# Power.net
KiCad netlist of a schematic drawn in Altium Designer
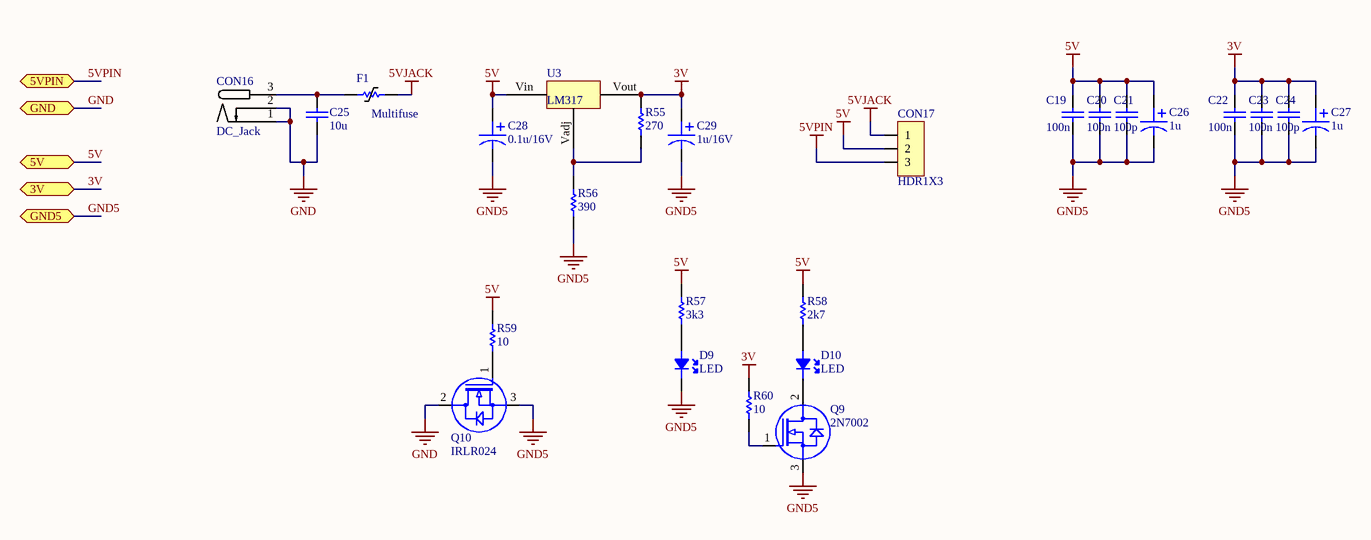
[diagram p0: Power.SchDoc]

(export (version "E")
  (design (tool "Eeschema 10.0.6"))
  (components
    (comp (ref "C19")
      (value "100n")
      (footprint "dimploma:0805C")
      (libsource (lib "diploma") (part "CAPACITOR"))
    )
    (comp (ref "C20")
      (value "100n")
      (footprint "dimploma:0805C")
      (libsource (lib "diploma") (part "CAPACITOR"))
    )
    (comp (ref "C21")
      (value "100p")
      (footprint "dimploma:0805C")
      (libsource (lib "diploma") (part "CAPACITOR"))
    )
    (comp (ref "C22")
      (value "100n")
      (footprint "dimploma:0805C")
      (libsource (lib "diploma") (part "CAPACITOR"))
    )
    (comp (ref "C23")
      (value "100n")
      (footprint "dimploma:0805C")
      (libsource (lib "diploma") (part "CAPACITOR"))
    )
    (comp (ref "C24")
      (value "100p")
      (footprint "dimploma:0805C")
      (libsource (lib "diploma") (part "CAPACITOR"))
    )
    (comp (ref "C25")
      (value "10u")
      (footprint "dimploma:0805C")
      (libsource (lib "diploma") (part "CAPACITOR"))
    )
    (comp (ref "C26")
      (value "1u")
      (footprint "dimploma:CA")
      (libsource (lib "diploma") (part "ELECTROLYTIC_CAPACITOR"))
    )
    (comp (ref "C27")
      (value "1u")
      (footprint "dimploma:CA")
      (libsource (lib "diploma") (part "ELECTROLYTIC_CAPACITOR"))
    )
    (comp (ref "C28")
      (value "0.1u/16V")
      (footprint "dimploma:CA")
      (libsource (lib "diploma") (part "ELECTROLYTIC_CAPACITOR"))
    )
    (comp (ref "C29")
      (value "1u/16V")
      (footprint "dimploma:CA")
      (libsource (lib "diploma") (part "ELECTROLYTIC_CAPACITOR"))
    )
    (comp (ref "CON16")
      (value "DC_Jack")
      (footprint "dimploma:DC_JACK_CIRCLE")
      (libsource (lib "diploma") (part "DC_Jack"))
    )
    (comp (ref "CON17")
      (value "HDR1X3")
      (footprint "dimploma:HDR1X3RAST")
      (libsource (lib "diploma") (part "HDR1X3"))
    )
    (comp (ref "D9") (value "LED") (footprint "dimploma:0805LED") (libsource (lib "diploma") (part "LED")))
    (comp (ref "D10") (value "LED") (footprint "dimploma:0805LED") (libsource (lib "diploma") (part "LED")))
    (comp (ref "F1")
      (value "Multifuse")
      (footprint "dimploma:1210FUSE")
      (libsource (lib "diploma") (part "Multifuse"))
    )
    (comp (ref "Q9")
      (value "2N7002")
      (footprint "dimploma:SOT23")
      (libsource (lib "diploma") (part "2N7002"))
    )
    (comp (ref "Q10")
      (value "IRLR024")
      (footprint "dimploma:TO-252AA")
      (libsource (lib "diploma") (part "IRLR024"))
    )
    (comp (ref "R55")
      (value "270")
      (footprint "dimploma:0805R")
      (libsource (lib "diploma") (part "RESISTOR"))
    )
    (comp (ref "R56")
      (value "390")
      (footprint "dimploma:0805R")
      (libsource (lib "diploma") (part "RESISTOR"))
    )
    (comp (ref "R57")
      (value "3k3")
      (footprint "dimploma:0805R")
      (libsource (lib "diploma") (part "RESISTOR"))
    )
    (comp (ref "R58")
      (value "2k7")
      (footprint "dimploma:0805R")
      (libsource (lib "diploma") (part "RESISTOR"))
    )
    (comp (ref "R59") (value "10") (footprint "dimploma:0805R") (libsource (lib "diploma") (part "RESISTOR")))
    (comp (ref "R60") (value "10") (footprint "dimploma:0805R") (libsource (lib "diploma") (part "RESISTOR")))
    (comp (ref "U3") (value "LM317") (footprint "dimploma:DPAK-3") (libsource (lib "diploma") (part "LM317")))
  )
  (nets
    (net (code "1") (name "3V") (class "Default")
      (node (ref "C22") (pin "2") (pinfunction "2_2") (pintype "passive"))
      (node (ref "C23") (pin "2") (pinfunction "2_2") (pintype "passive"))
      (node (ref "C24") (pin "2") (pinfunction "2_2") (pintype "passive"))
      (node (ref "C27") (pin "1") (pinfunction "1_1") (pintype "passive"))
      (node (ref "C29") (pin "1") (pinfunction "1_1") (pintype "passive"))
      (node (ref "R55") (pin "2") (pinfunction "2_2") (pintype "passive"))
      (node (ref "R60") (pin "2") (pinfunction "2_2") (pintype "passive"))
      (node (ref "U3") (pin "Vout") (pinfunction "Vout_Vout") (pintype "passive"))
    )
    (net (code "2") (name "5V") (class "Default")
      (node (ref "C19") (pin "2") (pinfunction "2_2") (pintype "passive"))
      (node (ref "C20") (pin "2") (pinfunction "2_2") (pintype "passive"))
      (node (ref "C21") (pin "2") (pinfunction "2_2") (pintype "passive"))
      (node (ref "C26") (pin "1") (pinfunction "1_1") (pintype "passive"))
      (node (ref "C28") (pin "1") (pinfunction "1_1") (pintype "passive"))
      (node (ref "CON17") (pin "2") (pinfunction "2_2") (pintype "passive"))
      (node (ref "R57") (pin "2") (pinfunction "2_2") (pintype "passive"))
      (node (ref "R58") (pin "2") (pinfunction "2_2") (pintype "passive"))
      (node (ref "R59") (pin "2") (pinfunction "2_2") (pintype "passive"))
      (node (ref "U3") (pin "Vin") (pinfunction "Vin_Vin") (pintype "passive"))
    )
    (net (code "3") (name "5VJACK") (class "Default")
      (node (ref "CON17") (pin "1") (pinfunction "1_1") (pintype "passive"))
      (node (ref "F1") (pin "2") (pinfunction "2_2") (pintype "passive"))
    )
    (net (code "4") (name "5VPIN") (class "Default")
      (node (ref "CON17") (pin "3") (pinfunction "3_3") (pintype "passive"))
    )
    (net (code "5") (name "GND") (class "Default")
      (node (ref "C25") (pin "1") (pinfunction "1_1") (pintype "passive"))
      (node (ref "CON16") (pin "1") (pinfunction "1_1") (pintype "passive"))
      (node (ref "CON16") (pin "2") (pinfunction "2_2") (pintype "passive"))
      (node (ref "Q10") (pin "2") (pinfunction "DRAIN_2") (pintype "passive"))
    )
    (net (code "6") (name "GND5") (class "Default")
      (node (ref "C19") (pin "1") (pinfunction "1_1") (pintype "passive"))
      (node (ref "C20") (pin "1") (pinfunction "1_1") (pintype "passive"))
      (node (ref "C21") (pin "1") (pinfunction "1_1") (pintype "passive"))
      (node (ref "C22") (pin "1") (pinfunction "1_1") (pintype "passive"))
      (node (ref "C23") (pin "1") (pinfunction "1_1") (pintype "passive"))
      (node (ref "C24") (pin "1") (pinfunction "1_1") (pintype "passive"))
      (node (ref "C26") (pin "2") (pinfunction "2_2") (pintype "passive"))
      (node (ref "C27") (pin "2") (pinfunction "2_2") (pintype "passive"))
      (node (ref "C28") (pin "2") (pinfunction "2_2") (pintype "passive"))
      (node (ref "C29") (pin "2") (pinfunction "2_2") (pintype "passive"))
      (node (ref "D9") (pin "2") (pinfunction "K_2") (pintype "passive"))
      (node (ref "Q10") (pin "3") (pinfunction "SOURCE_3") (pintype "passive"))
      (node (ref "Q9") (pin "3") (pinfunction "SOURCE_3") (pintype "passive"))
      (node (ref "R56") (pin "1") (pinfunction "1_1") (pintype "passive"))
    )
    (net (code "7") (name "Net-(C25-Pad2)") (class "Default")
      (node (ref "C25") (pin "2") (pinfunction "2_2") (pintype "passive"))
      (node (ref "CON16") (pin "3") (pinfunction "3_3") (pintype "passive"))
      (node (ref "F1") (pin "1") (pinfunction "1_1") (pintype "passive"))
    )
    (net (code "8") (name "Net-(D9-A)") (class "Default")
      (node (ref "D9") (pin "1") (pinfunction "A_1") (pintype "passive"))
      (node (ref "R57") (pin "1") (pinfunction "1_1") (pintype "passive"))
    )
    (net (code "9") (name "Net-(D10-A)") (class "Default")
      (node (ref "D10") (pin "1") (pinfunction "A_1") (pintype "passive"))
      (node (ref "R58") (pin "1") (pinfunction "1_1") (pintype "passive"))
    )
    (net (code "10") (name "Net-(D10-K)") (class "Default")
      (node (ref "D10") (pin "2") (pinfunction "K_2") (pintype "passive"))
      (node (ref "Q9") (pin "2") (pinfunction "DRAIN_2") (pintype "passive"))
    )
    (net (code "11") (name "Net-(Q9-GATE)") (class "Default")
      (node (ref "Q9") (pin "1") (pinfunction "GATE_1") (pintype "passive"))
      (node (ref "R60") (pin "1") (pinfunction "1_1") (pintype "passive"))
    )
    (net (code "12") (name "Net-(Q10-GATE)") (class "Default")
      (node (ref "Q10") (pin "1") (pinfunction "GATE_1") (pintype "passive"))
      (node (ref "R59") (pin "1") (pinfunction "1_1") (pintype "passive"))
    )
    (net (code "13") (name "Net-(R55-Pad1)") (class "Default")
      (node (ref "R55") (pin "1") (pinfunction "1_1") (pintype "passive"))
      (node (ref "R56") (pin "2") (pinfunction "2_2") (pintype "passive"))
      (node (ref "U3") (pin "Vadj") (pinfunction "Vadj_Vadj") (pintype "passive"))
    )
  )
)
